# PM12_X5.net
KiCad netlist of a schematic drawn in Altium Designer
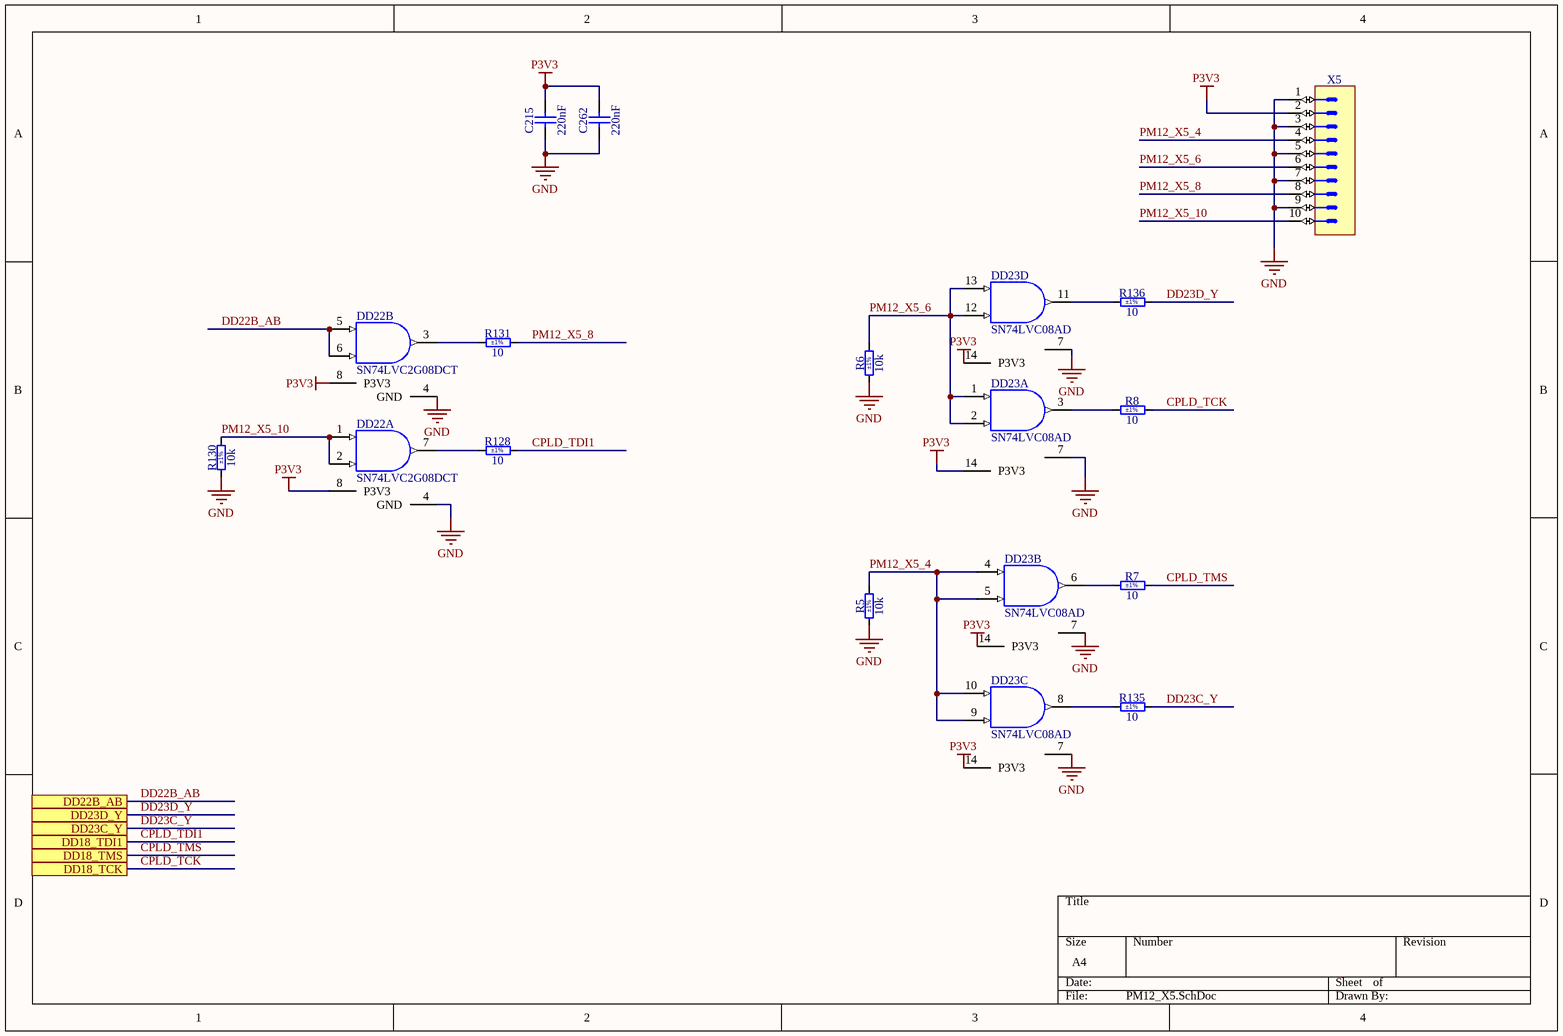
[diagram p0: PM12_X5.SchDoc]

(export (version "E")
  (design (tool "Eeschema 10.0.6"))
  (components
    (comp (ref "C215")
      (value "220nF")
      (footprint "CAPC2012X135N")
      (description "Non-polarised capacitor")
      (fields
        (field (name "PART NUMBER") "CC0805_220NF_50V_10%_X7R")
        (field (name "VOLTAGE") "50V")
        (field (name "AUTHOR") "CERN DEM JLC")
      )
      (libsource (lib "Capacitors") (part "Capacitor - non polarized"))
    )
    (comp (ref "C262")
      (value "220nF")
      (footprint "CAPC2012X135N")
      (description "Non-polarised capacitor")
      (fields
        (field (name "PART NUMBER") "CC0805_220NF_50V_10%_X7R")
        (field (name "VOLTAGE") "50V")
        (field (name "AUTHOR") "CERN DEM JLC")
      )
      (libsource (lib "Capacitors") (part "Capacitor - non polarized"))
    )
    (comp (ref "DD22")
      (value "SN74LVC2G08DCT")
      (footprint "SOP65P400X130-8N")
      (description "Dual 2-Input Positive AND Gate")
      (fields (field (name "MANUFACTURER") "TEXAS INSTRUMENTS") (field (name "AUTHOR") "CERN DEM MR"))
      (libsource (lib "ICs And Semiconductors") (part "742G08"))
    )
    (comp (ref "DD23")
      (value "SN74LVC08AD")
      (footprint "SOIC127P600X175-14N")
      (description "Quad 2-Input AND Gate")
      (fields (field (name "MANUFACTURER") "TEXAS INSTRUMENTS") (field (name "AUTHOR") "CERN DEM JLC"))
      (libsource (lib "ICs And Semiconductors") (part "7408"))
    )
    (comp (ref "R5")
      (value "10k")
      (footprint "RESC2012X60N")
      (description "Resistor - 1%")
      (fields
        (field (name "TOLERANCE") "±1%")
        (field (name "PART NUMBER") "R0805_10K_1%_0.125W_100PPM")
        (field (name "POWER") "0.125W")
        (field (name "AUTHOR") "CERN DEM JLC")
      )
      (libsource (lib "Resistors") (part "Resistor - 1%"))
    )
    (comp (ref "R6")
      (value "10k")
      (footprint "RESC2012X60N")
      (description "Resistor - 1%")
      (fields
        (field (name "TOLERANCE") "±1%")
        (field (name "PART NUMBER") "R0805_10K_1%_0.125W_100PPM")
        (field (name "POWER") "0.125W")
        (field (name "AUTHOR") "CERN DEM JLC")
      )
      (libsource (lib "Resistors") (part "Resistor - 1%"))
    )
    (comp (ref "R7")
      (value "10")
      (footprint "RESC2012X70N")
      (description "Resistor - 1%")
      (fields
        (field (name "TOLERANCE") "±1%")
        (field (name "PART NUMBER") "R0805_10R_1%_0.125W_100PPM_PANASONIC_ERJ")
        (field (name "POWER") "0.125W")
        (field (name "AUTHOR") "CERN DEM HF")
      )
      (libsource (lib "Resistors") (part "Resistor - 1%"))
    )
    (comp (ref "R8")
      (value "10")
      (footprint "RESC2012X70N")
      (description "Resistor - 1%")
      (fields
        (field (name "TOLERANCE") "±1%")
        (field (name "PART NUMBER") "R0805_10R_1%_0.125W_100PPM_PANASONIC_ERJ")
        (field (name "POWER") "0.125W")
        (field (name "AUTHOR") "CERN DEM HF")
      )
      (libsource (lib "Resistors") (part "Resistor - 1%"))
    )
    (comp (ref "R128")
      (value "10")
      (footprint "RESC2012X70N")
      (description "Resistor - 1%")
      (fields
        (field (name "TOLERANCE") "±1%")
        (field (name "PART NUMBER") "R0805_10R_1%_0.125W_100PPM_PANASONIC_ERJ")
        (field (name "POWER") "0.125W")
        (field (name "AUTHOR") "CERN DEM HF")
      )
      (libsource (lib "Resistors") (part "Resistor - 1%"))
    )
    (comp (ref "R130")
      (value "10k")
      (footprint "RESC2012X60N")
      (description "Resistor - 1%")
      (fields
        (field (name "TOLERANCE") "±1%")
        (field (name "PART NUMBER") "R0805_10K_1%_0.125W_100PPM")
        (field (name "POWER") "0.125W")
        (field (name "AUTHOR") "CERN DEM JLC")
      )
      (libsource (lib "Resistors") (part "Resistor - 1%"))
    )
    (comp (ref "R131")
      (value "10")
      (footprint "RESC2012X70N")
      (description "Resistor - 1%")
      (fields
        (field (name "TOLERANCE") "±1%")
        (field (name "PART NUMBER") "R0805_10R_1%_0.125W_100PPM_PANASONIC_ERJ")
        (field (name "POWER") "0.125W")
        (field (name "AUTHOR") "CERN DEM HF")
      )
      (libsource (lib "Resistors") (part "Resistor - 1%"))
    )
    (comp (ref "R135")
      (value "10")
      (footprint "RESC2012X70N")
      (description "Resistor - 1%")
      (fields
        (field (name "TOLERANCE") "±1%")
        (field (name "PART NUMBER") "R0805_10R_1%_0.125W_100PPM_PANASONIC_ERJ")
        (field (name "POWER") "0.125W")
        (field (name "AUTHOR") "CERN DEM HF")
      )
      (libsource (lib "Resistors") (part "Resistor - 1%"))
    )
    (comp (ref "R136")
      (value "10")
      (footprint "RESC2012X70N")
      (description "Resistor - 1%")
      (fields
        (field (name "TOLERANCE") "±1%")
        (field (name "PART NUMBER") "R0805_10R_1%_0.125W_100PPM_PANASONIC_ERJ")
        (field (name "POWER") "0.125W")
        (field (name "AUTHOR") "CERN DEM HF")
      )
      (libsource (lib "Resistors") (part "Resistor - 1%"))
    )
    (comp (ref "X5")
      (value "~")
      (footprint "CONNFLY_DS1014-10SF1B-B")
      (description "Connector 10 Male")
      (fields
        (field (name "PART NUMBER") "CONNFLY_DS1014-10SF1B-B")
        (field (name "MANUFACTURER") "CONNFLY")
        (field (name "AUTHOR") "CERN DEM HF")
      )
      (libsource (lib "Connectors") (part "Connector 10 Male"))
    )
  )
  (nets
    (net (code "1") (name "/CPLD_TCK") (class "Default")
      (node (ref "R8") (pin "2") (pinfunction "2_2") (pintype "passive"))
    )
    (net (code "2") (name "/CPLD_TDI1") (class "Default")
      (node (ref "R128") (pin "2") (pinfunction "2_2") (pintype "passive"))
    )
    (net (code "3") (name "/CPLD_TMS") (class "Default")
      (node (ref "R7") (pin "2") (pinfunction "2_2") (pintype "passive"))
    )
    (net (code "4") (name "/DD22B_AB") (class "Default")
      (node (ref "DD22") (pin "5") (pinfunction "A_5") (pintype "input"))
      (node (ref "DD22") (pin "6") (pinfunction "B_6") (pintype "input"))
    )
    (net (code "5") (name "/DD23C_Y") (class "Default")
      (node (ref "R135") (pin "2") (pinfunction "2_2") (pintype "passive"))
    )
    (net (code "6") (name "/DD23D_Y") (class "Default")
      (node (ref "R136") (pin "2") (pinfunction "2_2") (pintype "passive"))
    )
    (net (code "7") (name "/PM12_X5_4") (class "Default")
      (node (ref "DD23") (pin "10") (pinfunction "A_10") (pintype "input"))
      (node (ref "DD23") (pin "4") (pinfunction "A_4") (pintype "input"))
      (node (ref "DD23") (pin "5") (pinfunction "B_5") (pintype "input"))
      (node (ref "DD23") (pin "9") (pinfunction "B_9") (pintype "input"))
      (node (ref "R5") (pin "2") (pinfunction "2_2") (pintype "passive"))
      (node (ref "X5") (pin "4") (pinfunction "4_4") (pintype "bidirectional"))
    )
    (net (code "8") (name "/PM12_X5_6") (class "Default")
      (node (ref "DD23") (pin "1") (pinfunction "A_1") (pintype "input"))
      (node (ref "DD23") (pin "12") (pinfunction "B_12") (pintype "input"))
      (node (ref "DD23") (pin "13") (pinfunction "A_13") (pintype "input"))
      (node (ref "DD23") (pin "2") (pinfunction "B_2") (pintype "input"))
      (node (ref "R6") (pin "2") (pinfunction "2_2") (pintype "passive"))
      (node (ref "X5") (pin "6") (pinfunction "6_6") (pintype "bidirectional"))
    )
    (net (code "9") (name "/PM12_X5_8") (class "Default")
      (node (ref "R131") (pin "2") (pinfunction "2_2") (pintype "passive"))
      (node (ref "X5") (pin "8") (pinfunction "8_8") (pintype "bidirectional"))
    )
    (net (code "10") (name "/PM12_X5_10") (class "Default")
      (node (ref "DD22") (pin "1") (pinfunction "A_1") (pintype "input"))
      (node (ref "DD22") (pin "2") (pinfunction "B_2") (pintype "input"))
      (node (ref "R130") (pin "2") (pinfunction "2_2") (pintype "passive"))
      (node (ref "X5") (pin "10") (pinfunction "10_10") (pintype "bidirectional"))
    )
    (net (code "11") (name "GND") (class "Default")
      (node (ref "C215") (pin "1") (pinfunction "1_1") (pintype "passive"))
      (node (ref "C262") (pin "1") (pinfunction "1_1") (pintype "passive"))
      (node (ref "DD22") (pin "4") (pinfunction "GND_4") (pintype "power_in"))
      (node (ref "DD23") (pin "7") (pinfunction "GND_7") (pintype "power_in"))
      (node (ref "R130") (pin "1") (pinfunction "1_1") (pintype "passive"))
      (node (ref "R5") (pin "1") (pinfunction "1_1") (pintype "passive"))
      (node (ref "R6") (pin "1") (pinfunction "1_1") (pintype "passive"))
      (node (ref "X5") (pin "1") (pinfunction "1_1") (pintype "bidirectional"))
      (node (ref "X5") (pin "3") (pinfunction "3_3") (pintype "bidirectional"))
      (node (ref "X5") (pin "5") (pinfunction "5_5") (pintype "bidirectional"))
      (node (ref "X5") (pin "7") (pinfunction "7_7") (pintype "bidirectional"))
      (node (ref "X5") (pin "9") (pinfunction "9_9") (pintype "bidirectional"))
    )
    (net (code "12") (name "Net-(DD22A-Y)") (class "Default")
      (node (ref "DD22") (pin "7") (pinfunction "Y_7") (pintype "output"))
      (node (ref "R128") (pin "1") (pinfunction "1_1") (pintype "passive"))
    )
    (net (code "13") (name "Net-(DD22B-Y)") (class "Default")
      (node (ref "DD22") (pin "3") (pinfunction "Y_3") (pintype "output"))
      (node (ref "R131") (pin "1") (pinfunction "1_1") (pintype "passive"))
    )
    (net (code "14") (name "Net-(DD23A-Y)") (class "Default")
      (node (ref "DD23") (pin "3") (pinfunction "Y_3") (pintype "output"))
      (node (ref "R8") (pin "1") (pinfunction "1_1") (pintype "passive"))
    )
    (net (code "15") (name "Net-(DD23B-Y)") (class "Default")
      (node (ref "DD23") (pin "6") (pinfunction "Y_6") (pintype "output"))
      (node (ref "R7") (pin "1") (pinfunction "1_1") (pintype "passive"))
    )
    (net (code "16") (name "Net-(DD23C-Y)") (class "Default")
      (node (ref "DD23") (pin "8") (pinfunction "Y_8") (pintype "output"))
      (node (ref "R135") (pin "1") (pinfunction "1_1") (pintype "passive"))
    )
    (net (code "17") (name "Net-(DD23D-Y)") (class "Default")
      (node (ref "DD23") (pin "11") (pinfunction "Y_11") (pintype "output"))
      (node (ref "R136") (pin "1") (pinfunction "1_1") (pintype "passive"))
    )
    (net (code "18") (name "P3V3") (class "Default")
      (node (ref "C215") (pin "2") (pinfunction "2_2") (pintype "passive"))
      (node (ref "C262") (pin "2") (pinfunction "2_2") (pintype "passive"))
      (node (ref "DD22") (pin "8") (pinfunction "P3V3_8") (pintype "power_in"))
      (node (ref "DD23") (pin "14") (pinfunction "P3V3_14") (pintype "power_in"))
      (node (ref "X5") (pin "2") (pinfunction "2_2") (pintype "bidirectional"))
    )
  )
)
